# bGeigie3.net
KiCad netlist of a schematic drawn in EAGLE
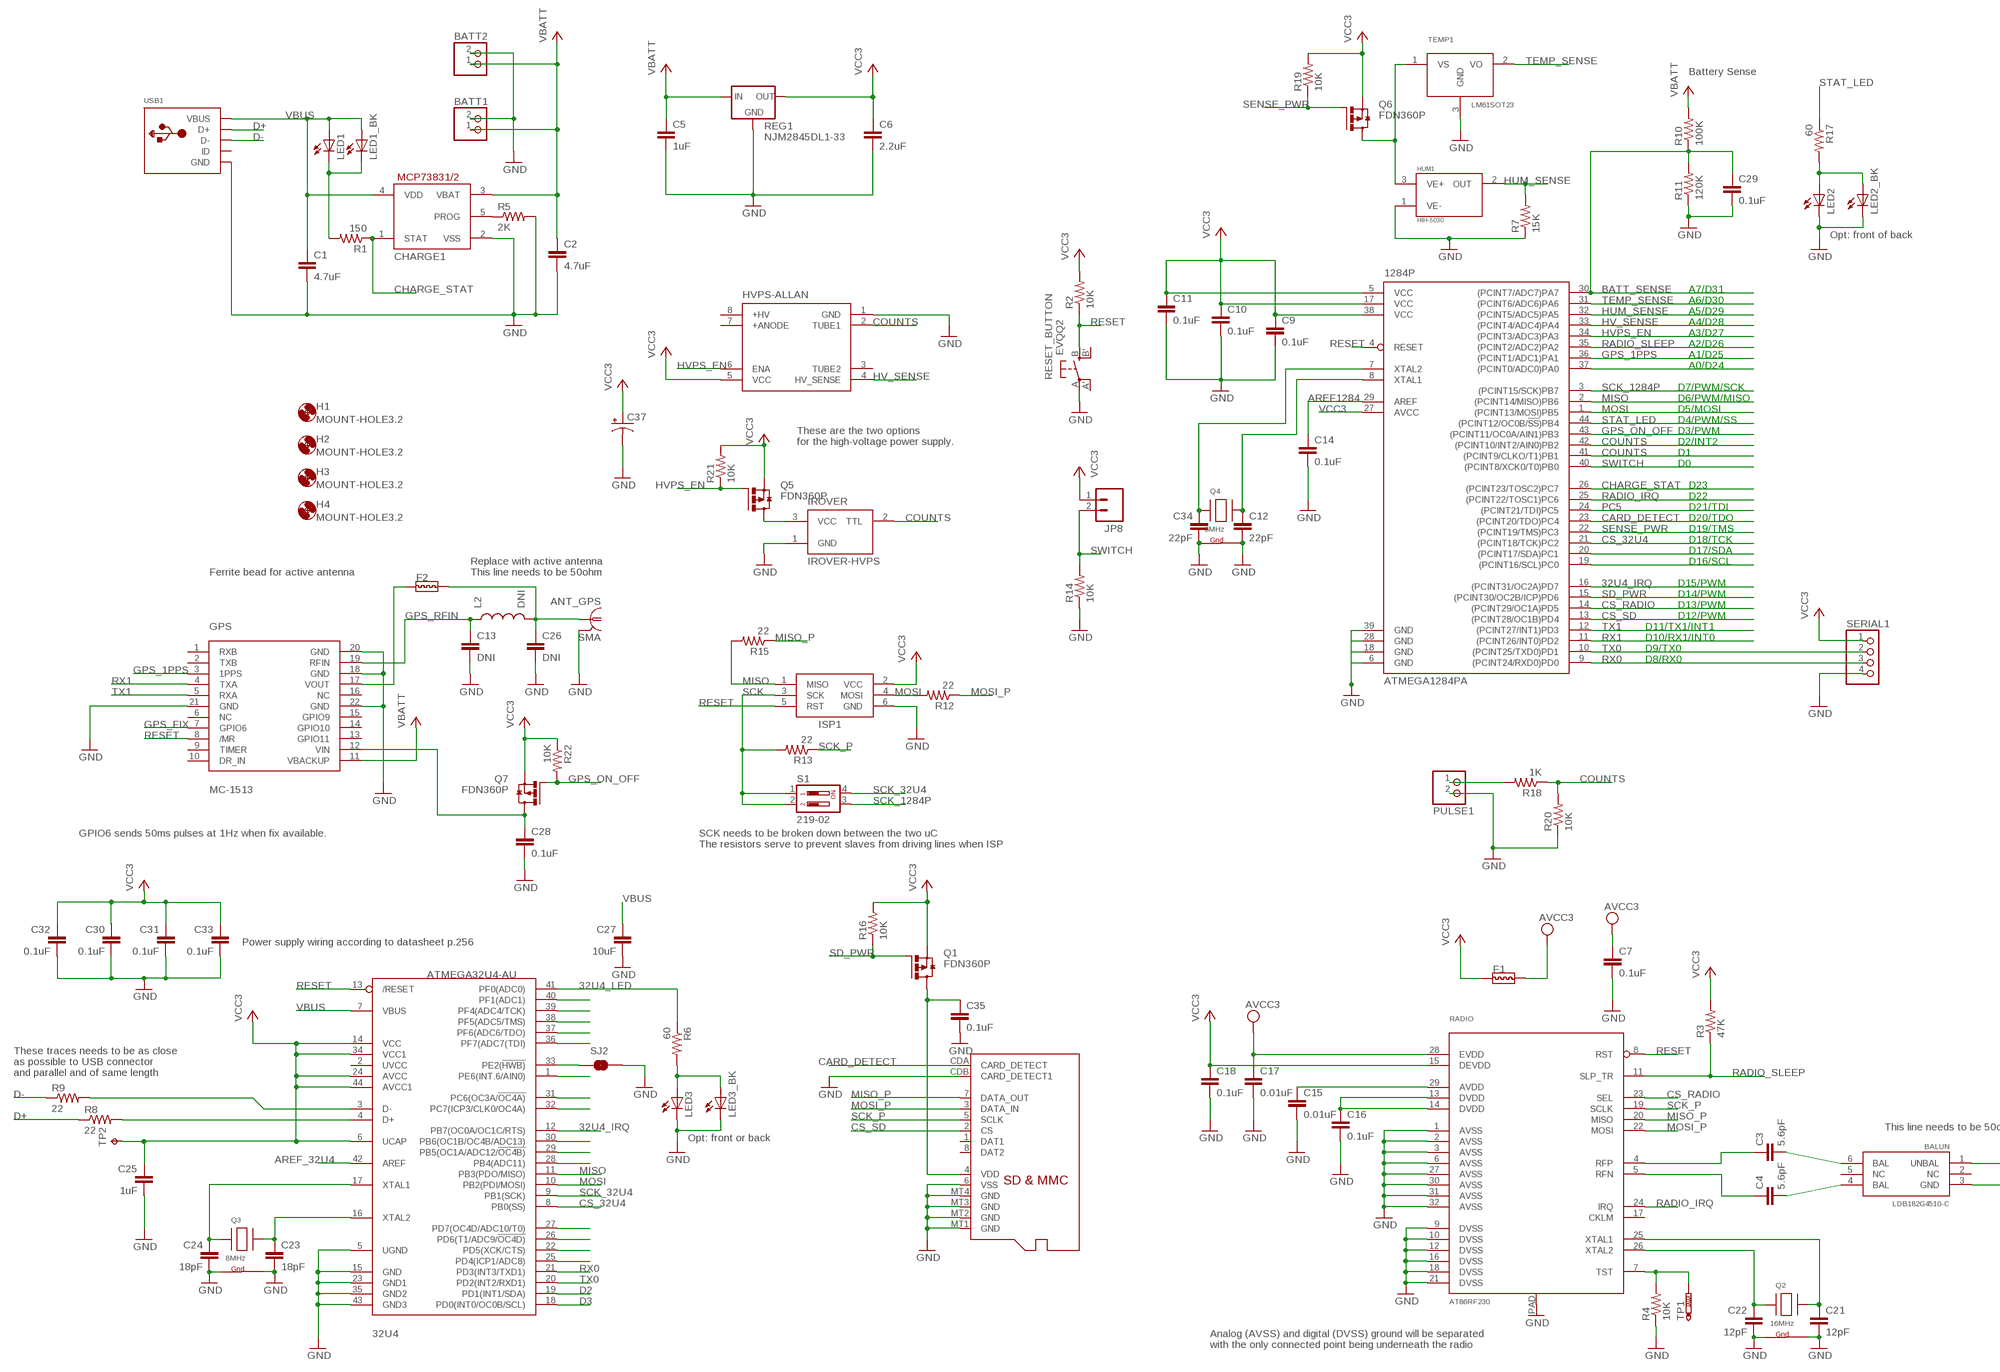
[diagram p0: schematic, sheet 1, part 1 of 2]
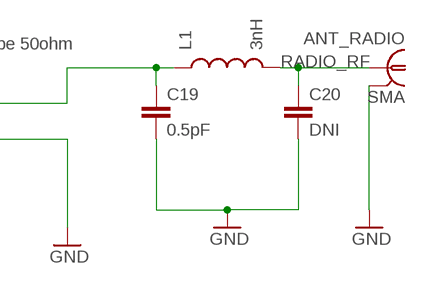
[diagram p1: schematic, sheet 1, part 2 of 2]

(export (version "E")
  (design (tool "Eeschema 10.0.6"))
  (components
    (comp (ref "32U4")
      (value "ATMEGA32U4-AU")
      (footprint "eagle-import:TQFP44")
      (libsource (lib "eagle-import") (part "ATMEGA32U4-AU"))
    )
    (comp (ref "1284P")
      (value "ATMEGA1284PA")
      (footprint "eagle-import:TQFP44")
      (fields (field (name "MPN") "ATMEGA644PV-10AU"))
      (libsource (lib "eagle-import") (part "ATMEGA1284PA"))
    )
    (comp (ref "ANT_GPS")
      (value "SMA")
      (footprint "eagle-import:LTI-SASF54GT")
      (libsource (lib "eagle-import") (part "LTI-SASF54GT"))
    )
    (comp (ref "ANT_RADIO")
      (value "SMA")
      (footprint "eagle-import:LTI-SASF54GT")
      (libsource (lib "eagle-import") (part "LTI-SASF54GT"))
    )
    (comp (ref "BALUN")
      (value "LDB182G4510-C")
      (footprint "eagle-import:LDB182G4510-C")
      (libsource (lib "eagle-import") (part "LDB182G4510-C"))
    )
    (comp (ref "BATT1")
      (value "JST_2PIN-THM")
      (footprint "eagle-import:JST-PH-2-THM")
      (libsource (lib "eagle-import") (part "JST_2PIN-THM"))
    )
    (comp (ref "BATT2")
      (value "JST_2PIN-THM")
      (footprint "eagle-import:JST-PH-2-THM")
      (libsource (lib "eagle-import") (part "JST_2PIN-THM"))
    )
    (comp (ref "C1")
      (value "4.7uF")
      (footprint "eagle-import:0805")
      (libsource (lib "eagle-import") (part "CAP0805"))
    )
    (comp (ref "C2")
      (value "4.7uF")
      (footprint "eagle-import:0805")
      (libsource (lib "eagle-import") (part "CAP0805"))
    )
    (comp (ref "C3")
      (value "5.6pF")
      (footprint "eagle-import:0402-CAP")
      (libsource (lib "eagle-import") (part "CAP0402-CAP"))
    )
    (comp (ref "C4")
      (value "5.6pF")
      (footprint "eagle-import:0402-CAP")
      (libsource (lib "eagle-import") (part "CAP0402-CAP"))
    )
    (comp (ref "C5")
      (value "1uF")
      (footprint "eagle-import:0805")
      (libsource (lib "eagle-import") (part "CAP0805"))
    )
    (comp (ref "C6")
      (value "2.2uF")
      (footprint "eagle-import:0805")
      (libsource (lib "eagle-import") (part "CAP0805"))
    )
    (comp (ref "C7")
      (value "0.1uF")
      (footprint "eagle-import:0603-CAP")
      (libsource (lib "eagle-import") (part "CAP0603-CAP"))
    )
    (comp (ref "C9")
      (value "0.1uF")
      (footprint "eagle-import:0603-CAP")
      (libsource (lib "eagle-import") (part "CAP0603-CAP"))
    )
    (comp (ref "C10")
      (value "0.1uF")
      (footprint "eagle-import:0603-CAP")
      (libsource (lib "eagle-import") (part "CAP0603-CAP"))
    )
    (comp (ref "C11")
      (value "0.1uF")
      (footprint "eagle-import:0603-CAP")
      (libsource (lib "eagle-import") (part "CAP0603-CAP"))
    )
    (comp (ref "C12")
      (value "22pF")
      (footprint "eagle-import:0603-CAP")
      (libsource (lib "eagle-import") (part "CAP0603-CAP"))
    )
    (comp (ref "C13")
      (value "DNI")
      (footprint "eagle-import:0402-CAP")
      (libsource (lib "eagle-import") (part "CAP0402-CAP"))
    )
    (comp (ref "C14")
      (value "0.1uF")
      (footprint "eagle-import:0603-CAP")
      (libsource (lib "eagle-import") (part "CAP0603-CAP"))
    )
    (comp (ref "C15")
      (value "0.01uF")
      (footprint "eagle-import:0603-CAP")
      (libsource (lib "eagle-import") (part "CAP0603-CAP"))
    )
    (comp (ref "C16")
      (value "0.1uF")
      (footprint "eagle-import:0603-CAP")
      (libsource (lib "eagle-import") (part "CAP0603-CAP"))
    )
    (comp (ref "C17")
      (value "0.01uF")
      (footprint "eagle-import:0603-CAP")
      (libsource (lib "eagle-import") (part "CAP0603-CAP"))
    )
    (comp (ref "C18")
      (value "0.1uF")
      (footprint "eagle-import:0603-CAP")
      (libsource (lib "eagle-import") (part "CAP0603-CAP"))
    )
    (comp (ref "C19")
      (value "0.5pF")
      (footprint "eagle-import:0402-CAP")
      (libsource (lib "eagle-import") (part "CAP0402-CAP"))
    )
    (comp (ref "C20")
      (value "DNI")
      (footprint "eagle-import:0402-CAP")
      (libsource (lib "eagle-import") (part "CAP0402-CAP"))
    )
    (comp (ref "C21")
      (value "12pF")
      (footprint "eagle-import:0603-CAP")
      (libsource (lib "eagle-import") (part "CAP0603-CAP"))
    )
    (comp (ref "C22")
      (value "12pF")
      (footprint "eagle-import:0603-CAP")
      (libsource (lib "eagle-import") (part "CAP0603-CAP"))
    )
    (comp (ref "C23")
      (value "18pF")
      (footprint "eagle-import:0603-CAP")
      (libsource (lib "eagle-import") (part "CAP0603-CAP"))
    )
    (comp (ref "C24")
      (value "18pF")
      (footprint "eagle-import:0603-CAP")
      (libsource (lib "eagle-import") (part "CAP0603-CAP"))
    )
    (comp (ref "C25")
      (value "1uF")
      (footprint "eagle-import:0603-CAP")
      (libsource (lib "eagle-import") (part "CAP0603-CAP"))
    )
    (comp (ref "C26")
      (value "DNI")
      (footprint "eagle-import:0402-CAP")
      (libsource (lib "eagle-import") (part "CAP0402-CAP"))
    )
    (comp (ref "C27")
      (value "10uF")
      (footprint "eagle-import:0805")
      (libsource (lib "eagle-import") (part "CAP0805"))
    )
    (comp (ref "C28")
      (value "0.1uF")
      (footprint "eagle-import:0603-CAP")
      (libsource (lib "eagle-import") (part "CAP0603-CAP"))
    )
    (comp (ref "C29")
      (value "0.1uF")
      (footprint "eagle-import:0603-CAP")
      (libsource (lib "eagle-import") (part "CAP0603-CAP"))
    )
    (comp (ref "C30")
      (value "0.1uF")
      (footprint "eagle-import:0603-CAP")
      (libsource (lib "eagle-import") (part "CAP0603-CAP"))
    )
    (comp (ref "C31")
      (value "0.1uF")
      (footprint "eagle-import:0603-CAP")
      (libsource (lib "eagle-import") (part "CAP0603-CAP"))
    )
    (comp (ref "C32")
      (value "0.1uF")
      (footprint "eagle-import:0603-CAP")
      (libsource (lib "eagle-import") (part "CAP0603-CAP"))
    )
    (comp (ref "C33")
      (value "0.1uF")
      (footprint "eagle-import:0603-CAP")
      (libsource (lib "eagle-import") (part "CAP0603-CAP"))
    )
    (comp (ref "C34")
      (value "22pF")
      (footprint "eagle-import:0603-CAP")
      (libsource (lib "eagle-import") (part "CAP0603-CAP"))
    )
    (comp (ref "C35")
      (value "0.1uF")
      (footprint "eagle-import:0603-CAP")
      (libsource (lib "eagle-import") (part "CAP0603-CAP"))
    )
    (comp (ref "C37")
      (value "CPOL-USD/7343-31W")
      (footprint "eagle-import:D_7343-31W")
      (libsource (lib "eagle-import") (part "CPOL-USD/7343-31W"))
    )
    (comp (ref "CHARGE1")
      (value "MCP73831/OT")
      (footprint "eagle-import:SOT23-5L")
      (libsource (lib "eagle-import") (part "MCP73831/OT"))
    )
    (comp (ref "F1")
      (value "L-FERRITE-BEAD-0805")
      (footprint "eagle-import:0805")
      (libsource (lib "eagle-import") (part "L-FERRITE-BEAD-0805"))
    )
    (comp (ref "F2")
      (value "L-FERRITE-BEAD-0805")
      (footprint "eagle-import:0805")
      (libsource (lib "eagle-import") (part "L-FERRITE-BEAD-0805"))
    )
    (comp (ref "GPS")
      (value "MC-1513")
      (footprint "eagle-import:S4-1513")
      (libsource (lib "eagle-import") (part "MC-1513"))
    )
    (comp (ref "H1")
      (value "MOUNT-HOLE3.2")
      (footprint "eagle-import:3,2")
      (libsource (lib "eagle-import") (part "MOUNT-HOLE3.2"))
    )
    (comp (ref "H2")
      (value "MOUNT-HOLE3.2")
      (footprint "eagle-import:3,2")
      (libsource (lib "eagle-import") (part "MOUNT-HOLE3.2"))
    )
    (comp (ref "H3")
      (value "MOUNT-HOLE3.2")
      (footprint "eagle-import:3,2")
      (libsource (lib "eagle-import") (part "MOUNT-HOLE3.2"))
    )
    (comp (ref "H4")
      (value "MOUNT-HOLE3.2")
      (footprint "eagle-import:3,2")
      (libsource (lib "eagle-import") (part "MOUNT-HOLE3.2"))
    )
    (comp (ref "HUM1")
      (value "HIH-5030")
      (footprint "eagle-import:HIH-5030")
      (libsource (lib "eagle-import") (part "HIH-5030"))
    )
    (comp (ref "HVPS-ALLAN")
      (value "HVPS-ALLANV2-REVERSE")
      (footprint "eagle-import:HVPS-ALLAN-V2-REVERSE")
      (libsource (lib "eagle-import") (part "HVPS-ALLANV2-REVERSE"))
    )
    (comp (ref "IROVER")
      (value "IROVER-HVPS")
      (footprint "eagle-import:IROVER")
      (libsource (lib "eagle-import") (part "IROVER-HVPS"))
    )
    (comp (ref "ISP1")
      (value "AVRISP-6")
      (footprint "eagle-import:AVRISP")
      (libsource (lib "eagle-import") (part "AVRISP-6"))
    )
    (comp (ref "JP8")
      (value "M023.5MM")
      (footprint "eagle-import:SCREWTERMINAL-3.5MM-2")
      (libsource (lib "eagle-import") (part "M023.5MM"))
    )
    (comp (ref "L1")
      (value "3nH")
      (footprint "eagle-import:C0402")
      (libsource (lib "eagle-import") (part "INDUCTOR0402"))
    )
    (comp (ref "L2")
      (value "DNI")
      (footprint "eagle-import:C0402")
      (libsource (lib "eagle-import") (part "INDUCTOR0402"))
    )
    (comp (ref "LED1")
      (value "LEDCHIPLED_0603")
      (footprint "eagle-import:CHIPLED_0603")
      (libsource (lib "eagle-import") (part "LEDCHIPLED_0603"))
    )
    (comp (ref "LED1_BK")
      (value "LEDCHIPLED_0603")
      (footprint "eagle-import:CHIPLED_0603")
      (libsource (lib "eagle-import") (part "LEDCHIPLED_0603"))
    )
    (comp (ref "LED2")
      (value "LEDCHIPLED_0603")
      (footprint "eagle-import:CHIPLED_0603")
      (libsource (lib "eagle-import") (part "LEDCHIPLED_0603"))
    )
    (comp (ref "LED2_BK")
      (value "LEDCHIPLED_0603")
      (footprint "eagle-import:CHIPLED_0603")
      (libsource (lib "eagle-import") (part "LEDCHIPLED_0603"))
    )
    (comp (ref "LED3")
      (value "LEDCHIPLED_0603")
      (footprint "eagle-import:CHIPLED_0603")
      (libsource (lib "eagle-import") (part "LEDCHIPLED_0603"))
    )
    (comp (ref "LED3_BK")
      (value "LEDCHIPLED_0603")
      (footprint "eagle-import:CHIPLED_0603")
      (libsource (lib "eagle-import") (part "LEDCHIPLED_0603"))
    )
    (comp (ref "PULSE1")
      (value "JST_2PIN-THM")
      (footprint "eagle-import:JST-PH-2-THM")
      (libsource (lib "eagle-import") (part "JST_2PIN-THM"))
    )
    (comp (ref "Q1")
      (value "FDN360P")
      (footprint "eagle-import:SUPER-SOT3")
      (libsource (lib "eagle-import") (part "FDN360P"))
    )
    (comp (ref "Q2")
      (value "16MHz")
      (footprint "eagle-import:NX3225")
      (libsource (lib "eagle-import") (part "XTAL-4-3225"))
    )
    (comp (ref "Q3")
      (value "8MHz")
      (footprint "eagle-import:CRYSTAL-5032")
      (libsource (lib "eagle-import") (part "XTAL-4"))
    )
    (comp (ref "Q4")
      (value "8MHz")
      (footprint "eagle-import:CRYSTAL-5032")
      (libsource (lib "eagle-import") (part "XTAL-4"))
    )
    (comp (ref "Q5")
      (value "FDN360P")
      (footprint "eagle-import:SUPER-SOT3")
      (libsource (lib "eagle-import") (part "FDN360P"))
    )
    (comp (ref "Q6")
      (value "FDN360P")
      (footprint "eagle-import:SUPER-SOT3")
      (libsource (lib "eagle-import") (part "FDN360P"))
    )
    (comp (ref "Q7")
      (value "FDN360P")
      (footprint "eagle-import:SUPER-SOT3")
      (libsource (lib "eagle-import") (part "FDN360P"))
    )
    (comp (ref "R1")
      (value "150")
      (footprint "eagle-import:R0805")
      (libsource (lib "eagle-import") (part "R-US_R0805"))
    )
    (comp (ref "R2")
      (value "10K")
      (footprint "eagle-import:R0603")
      (libsource (lib "eagle-import") (part "R-US_R0603"))
    )
    (comp (ref "R3")
      (value "47K")
      (footprint "eagle-import:R0603")
      (libsource (lib "eagle-import") (part "R-US_R0603"))
    )
    (comp (ref "R4")
      (value "10K")
      (footprint "eagle-import:R0603")
      (libsource (lib "eagle-import") (part "R-US_R0603"))
    )
    (comp (ref "R5")
      (value "2K")
      (footprint "eagle-import:R0603")
      (libsource (lib "eagle-import") (part "R-US_R0603"))
    )
    (comp (ref "R6")
      (value "60")
      (footprint "eagle-import:R0805")
      (libsource (lib "eagle-import") (part "R-US_R0805"))
    )
    (comp (ref "R7")
      (value "15K")
      (footprint "eagle-import:R0603")
      (libsource (lib "eagle-import") (part "R-US_R0603"))
    )
    (comp (ref "R8")
      (value "22")
      (footprint "eagle-import:R0603")
      (libsource (lib "eagle-import") (part "R-US_R0603"))
    )
    (comp (ref "R9")
      (value "22")
      (footprint "eagle-import:R0603")
      (libsource (lib "eagle-import") (part "R-US_R0603"))
    )
    (comp (ref "R10")
      (value "100K")
      (footprint "eagle-import:R0603")
      (libsource (lib "eagle-import") (part "R-US_R0603"))
    )
    (comp (ref "R11")
      (value "120K")
      (footprint "eagle-import:R0603")
      (libsource (lib "eagle-import") (part "R-US_R0603"))
    )
    (comp (ref "R12")
      (value "22")
      (footprint "eagle-import:R0603")
      (libsource (lib "eagle-import") (part "R-US_R0603"))
    )
    (comp (ref "R13")
      (value "22")
      (footprint "eagle-import:R0603")
      (libsource (lib "eagle-import") (part "R-US_R0603"))
    )
    (comp (ref "R14")
      (value "10K")
      (footprint "eagle-import:R0603")
      (libsource (lib "eagle-import") (part "R-US_R0603"))
    )
    (comp (ref "R15")
      (value "22")
      (footprint "eagle-import:R0603")
      (libsource (lib "eagle-import") (part "R-US_R0603"))
    )
    (comp (ref "R16")
      (value "10K")
      (footprint "eagle-import:R0603")
      (libsource (lib "eagle-import") (part "R-US_R0603"))
    )
    (comp (ref "R17")
      (value "60")
      (footprint "eagle-import:R0805")
      (libsource (lib "eagle-import") (part "R-US_R0805"))
    )
    (comp (ref "R18")
      (value "1K")
      (footprint "eagle-import:R0603")
      (libsource (lib "eagle-import") (part "R-US_R0603"))
    )
    (comp (ref "R19")
      (value "10K")
      (footprint "eagle-import:R0603")
      (libsource (lib "eagle-import") (part "R-US_R0603"))
    )
    (comp (ref "R20")
      (value "10K")
      (footprint "eagle-import:R0603")
      (libsource (lib "eagle-import") (part "R-US_R0603"))
    )
    (comp (ref "R21")
      (value "10K")
      (footprint "eagle-import:R0603")
      (libsource (lib "eagle-import") (part "R-US_R0603"))
    )
    (comp (ref "R22")
      (value "10K")
      (footprint "eagle-import:R0603")
      (libsource (lib "eagle-import") (part "R-US_R0603"))
    )
    (comp (ref "RADIO")
      (value "AT86RF230")
      (footprint "eagle-import:32QN1")
      (libsource (lib "eagle-import") (part "AT86RF230"))
    )
    (comp (ref "REG1")
      (value "NJM2845DL1-33")
      (footprint "eagle-import:DPACK")
      (libsource (lib "eagle-import") (part "LP2950?CDT-3.3"))
    )
    (comp (ref "RESET_BUTTON")
      (value "EVQQ2")
      (footprint "eagle-import:EVQ-Q2")
      (libsource (lib "eagle-import") (part "EVQQ2"))
    )
    (comp (ref "S1")
      (value "219-02")
      (footprint "eagle-import:CTS-219-02")
      (libsource (lib "eagle-import") (part "219-02"))
    )
    (comp (ref "SD")
      (value "MICROSD")
      (footprint "eagle-import:DM3AT-SF-PEJM5")
      (libsource (lib "eagle-import") (part "MICROSD"))
    )
    (comp (ref "SERIAL1")
      (value "PINHD-1X4")
      (footprint "eagle-import:1X04")
      (libsource (lib "eagle-import") (part "PINHD-1X4"))
    )
    (comp (ref "SJ2")
      (value "SOLDERJUMPERTRACE")
      (footprint "eagle-import:SJ_2S-TRACE")
      (libsource (lib "eagle-import") (part "SOLDERJUMPERTRACE"))
    )
    (comp (ref "TEMP1")
      (value "LM61SOT23")
      (footprint "eagle-import:SOT23")
      (libsource (lib "eagle-import") (part "LM61SOT23"))
    )
    (comp (ref "TP1")
      (value "PTR1B1,27")
      (footprint "eagle-import:B1,27")
      (libsource (lib "eagle-import") (part "PTR1B1,27"))
    )
    (comp (ref "TP2")
      (value "TPTP15SQ")
      (footprint "eagle-import:TP15SQ")
      (libsource (lib "eagle-import") (part "TPTP15SQ"))
    )
    (comp (ref "USB1")
      (value "USBMINIB")
      (footprint "eagle-import:USB-MINIB")
      (libsource (lib "eagle-import") (part "USBMINIB"))
    )
  )
  (nets
    (net (code "1") (name "/32U4_IRQ") (class "Default")
      (node (ref "1284P") (pin "16") (pinfunction "(PCINT31/OC2A)PD7_16") (pintype "bidirectional"))
      (node (ref "32U4") (pin "12") (pinfunction "PB7(OC0A/OC1C/RTS)_12") (pintype "bidirectional"))
    )
    (net (code "2") (name "/32U4_LED") (class "Default")
      (node (ref "32U4") (pin "41") (pinfunction "PF0(ADC0)_41") (pintype "bidirectional"))
      (node (ref "R6") (pin "1") (pinfunction "1_1") (pintype "passive"))
    )
    (net (code "3") (name "/AREF1284") (class "Default")
      (node (ref "1284P") (pin "29") (pinfunction "AREF_29") (pintype "passive"))
      (node (ref "C14") (pin "1") (pinfunction "1_1") (pintype "passive"))
    )
    (net (code "4") (name "/AREF_32U4") (class "Default")
      (node (ref "32U4") (pin "42") (pinfunction "AREF_42") (pintype "bidirectional"))
    )
    (net (code "5") (name "/BATT_SENSE") (class "Default")
      (node (ref "1284P") (pin "30") (pinfunction "(PCINT7/ADC7)PA7_30") (pintype "bidirectional"))
      (node (ref "C29") (pin "1") (pinfunction "1_1") (pintype "passive"))
      (node (ref "R10") (pin "1") (pinfunction "1_1") (pintype "passive"))
      (node (ref "R11") (pin "2") (pinfunction "2_2") (pintype "passive"))
    )
    (net (code "6") (name "/CARD_DETECT") (class "Default")
      (node (ref "1284P") (pin "23") (pinfunction "(PCINT20/TDO)PC4_23") (pintype "output"))
      (node (ref "SD") (pin "CDA") (pinfunction "CARD_DETECT_CDA") (pintype "passive"))
    )
    (net (code "7") (name "/CHARGE_STAT") (class "Default")
      (node (ref "1284P") (pin "26") (pinfunction "(PCINT23/TOSC2)PC7_26") (pintype "output"))
      (node (ref "CHARGE1") (pin "1") (pinfunction "STAT_1") (pintype "output"))
      (node (ref "R1") (pin "1") (pinfunction "1_1") (pintype "passive"))
    )
    (net (code "8") (name "/COUNTS") (class "Default")
      (node (ref "1284P") (pin "41") (pinfunction "(PCINT9/CLKO/T1)PB1_41") (pintype "bidirectional"))
      (node (ref "1284P") (pin "42") (pinfunction "(PCINT10/INT2/AIN0)PB2_42") (pintype "bidirectional"))
      (node (ref "HVPS-ALLAN") (pin "2") (pinfunction "TUBE1_2") (pintype "bidirectional"))
      (node (ref "IROVER") (pin "2") (pinfunction "TTL_2") (pintype "bidirectional"))
      (node (ref "R18") (pin "1") (pinfunction "1_1") (pintype "passive"))
      (node (ref "R20") (pin "2") (pinfunction "2_2") (pintype "passive"))
    )
    (net (code "9") (name "/CS_32U4") (class "Default")
      (node (ref "1284P") (pin "21") (pinfunction "(PCINT18/TCK)PC2_21") (pintype "output"))
      (node (ref "32U4") (pin "8") (pinfunction "PB0(SS)_8") (pintype "bidirectional"))
    )
    (net (code "10") (name "/CS_RADIO") (class "Default")
      (node (ref "1284P") (pin "14") (pinfunction "(PCINT29/OC1A)PD5_14") (pintype "bidirectional"))
      (node (ref "RADIO") (pin "23") (pinfunction "SEL_23") (pintype "bidirectional"))
    )
    (net (code "11") (name "/CS_SD") (class "Default")
      (node (ref "1284P") (pin "13") (pinfunction "(PCINT28/OC1B)PD4_13") (pintype "bidirectional"))
      (node (ref "SD") (pin "2") (pinfunction "CS_2") (pintype "input"))
    )
    (net (code "12") (name "/D+") (class "Default")
      (node (ref "R8") (pin "1") (pinfunction "1_1") (pintype "passive"))
      (node (ref "USB1") (pin "D+") (pinfunction "D+_D+") (pintype "bidirectional"))
    )
    (net (code "13") (name "/D-") (class "Default")
      (node (ref "R9") (pin "1") (pinfunction "1_1") (pintype "passive"))
      (node (ref "USB1") (pin "D-") (pinfunction "D-_D-") (pintype "bidirectional"))
    )
    (net (code "14") (name "/D2") (class "Default")
      (node (ref "32U4") (pin "19") (pinfunction "PD1(INT1/SDA)_19") (pintype "bidirectional"))
    )
    (net (code "15") (name "/D3") (class "Default")
      (node (ref "32U4") (pin "18") (pinfunction "PD0(INT0/OC0B/SCL)_18") (pintype "bidirectional"))
    )
    (net (code "16") (name "/GPS_1PPS") (class "Default")
      (node (ref "1284P") (pin "36") (pinfunction "(PCINT1/ADC1)PA1_36") (pintype "bidirectional"))
      (node (ref "GPS") (pin "3") (pinfunction "1PPS_3") (pintype "bidirectional"))
    )
    (net (code "17") (name "/GPS_FIX") (class "Default")
      (node (ref "GPS") (pin "7") (pinfunction "GPIO6_7") (pintype "bidirectional"))
    )
    (net (code "18") (name "/GPS_ON_OFF") (class "Default")
      (node (ref "1284P") (pin "43") (pinfunction "(PCINT11/OC0A/AIN1)PB3_43") (pintype "bidirectional"))
      (node (ref "Q7") (pin "1") (pinfunction "G_1") (pintype "passive"))
      (node (ref "R22") (pin "2") (pinfunction "2_2") (pintype "passive"))
    )
    (net (code "19") (name "/GPS_RFIN") (class "Default")
      (node (ref "C13") (pin "1") (pinfunction "1_1") (pintype "passive"))
      (node (ref "GPS") (pin "19") (pinfunction "RFIN_19") (pintype "bidirectional"))
      (node (ref "L2") (pin "1") (pinfunction "1_1") (pintype "passive"))
    )
    (net (code "20") (name "/HUM_SENSE") (class "Default")
      (node (ref "1284P") (pin "32") (pinfunction "(PCINT5/ADC5)PA5_32") (pintype "bidirectional"))
      (node (ref "HUM1") (pin "2") (pinfunction "OUT_2") (pintype "bidirectional"))
      (node (ref "R7") (pin "2") (pinfunction "2_2") (pintype "passive"))
    )
    (net (code "21") (name "/HVPS_EN") (class "Default")
      (node (ref "1284P") (pin "34") (pinfunction "(PCINT3/ADC3)PA3_34") (pintype "bidirectional"))
      (node (ref "HVPS-ALLAN") (pin "6") (pinfunction "ENA_6") (pintype "bidirectional"))
      (node (ref "Q5") (pin "1") (pinfunction "G_1") (pintype "passive"))
      (node (ref "R21") (pin "1") (pinfunction "1_1") (pintype "passive"))
    )
    (net (code "22") (name "/HV_SENSE") (class "Default")
      (node (ref "1284P") (pin "33") (pinfunction "(PCINT4/ADC4)PA4_33") (pintype "bidirectional"))
      (node (ref "HVPS-ALLAN") (pin "4") (pinfunction "HV_SENSE_4") (pintype "bidirectional"))
    )
    (net (code "23") (name "/MISO") (class "Default")
      (node (ref "1284P") (pin "2") (pinfunction "(PCINT14/MISO)PB6_2") (pintype "bidirectional"))
      (node (ref "32U4") (pin "11") (pinfunction "PB3(PDO/MISO)_11") (pintype "bidirectional"))
      (node (ref "ISP1") (pin "1") (pinfunction "MISO_1") (pintype "input"))
      (node (ref "R15") (pin "2") (pinfunction "2_2") (pintype "passive"))
    )
    (net (code "24") (name "/MISO_P") (class "Default")
      (node (ref "R15") (pin "1") (pinfunction "1_1") (pintype "passive"))
      (node (ref "RADIO") (pin "20") (pinfunction "MISO_20") (pintype "bidirectional"))
      (node (ref "SD") (pin "7") (pinfunction "DATA_OUT_7") (pintype "output"))
    )
    (net (code "25") (name "/MOSI") (class "Default")
      (node (ref "1284P") (pin "1") (pinfunction "(PCINT13/MOSI)PB5_1") (pintype "bidirectional"))
      (node (ref "32U4") (pin "10") (pinfunction "PB2(PDI/MOSI)_10") (pintype "bidirectional"))
      (node (ref "ISP1") (pin "4") (pinfunction "MOSI_4") (pintype "output"))
      (node (ref "R12") (pin "2") (pinfunction "2_2") (pintype "passive"))
    )
    (net (code "26") (name "/MOSI_P") (class "Default")
      (node (ref "R12") (pin "1") (pinfunction "1_1") (pintype "passive"))
      (node (ref "RADIO") (pin "22") (pinfunction "MOSI_22") (pintype "bidirectional"))
      (node (ref "SD") (pin "3") (pinfunction "DATA_IN_3") (pintype "input"))
    )
    (net (code "27") (name "/PC5") (class "Default")
      (node (ref "1284P") (pin "24") (pinfunction "(PCINT21/TDI)PC5_24") (pintype "output"))
    )
    (net (code "28") (name "/RADIO_IRQ") (class "Default")
      (node (ref "1284P") (pin "25") (pinfunction "(PCINT22/TOSC1)PC6_25") (pintype "output"))
      (node (ref "RADIO") (pin "24") (pinfunction "IRQ_24") (pintype "bidirectional"))
    )
    (net (code "29") (name "/RADIO_RF") (class "Default")
      (node (ref "ANT_RADIO") (pin "1") (pinfunction "1_1") (pintype "passive"))
      (node (ref "C20") (pin "1") (pinfunction "1_1") (pintype "passive"))
      (node (ref "L1") (pin "2") (pinfunction "2_2") (pintype "passive"))
    )
    (net (code "30") (name "/RADIO_SLEEP") (class "Default")
      (node (ref "1284P") (pin "35") (pinfunction "(PCINT2/ADC2)PA2_35") (pintype "bidirectional"))
      (node (ref "R3") (pin "1") (pinfunction "1_1") (pintype "passive"))
      (node (ref "RADIO") (pin "11") (pinfunction "SLP_TR_11") (pintype "bidirectional"))
    )
    (net (code "31") (name "/RESET") (class "Default")
      (node (ref "1284P") (pin "4") (pinfunction "RESET_4") (pintype "input"))
      (node (ref "32U4") (pin "13") (pinfunction "/RESET_13") (pintype "bidirectional"))
      (node (ref "GPS") (pin "8") (pinfunction "/MR_8") (pintype "bidirectional"))
      (node (ref "ISP1") (pin "5") (pinfunction "RST_5") (pintype "output"))
      (node (ref "R2") (pin "1") (pinfunction "1_1") (pintype "passive"))
      (node (ref "RADIO") (pin "8") (pinfunction "RST_8") (pintype "input"))
      (node (ref "RESET_BUTTON") (pin "B") (pinfunction "S_B") (pintype "passive"))
    )
    (net (code "32") (name "/RX0") (class "Default")
      (node (ref "1284P") (pin "9") (pinfunction "(PCINT24/RXD0)PD0_9") (pintype "bidirectional"))
      (node (ref "32U4") (pin "21") (pinfunction "PD3(INT3/TXD1)_21") (pintype "bidirectional"))
      (node (ref "SERIAL1") (pin "3") (pinfunction "3_3") (pintype "passive"))
    )
    (net (code "33") (name "/RX1") (class "Default")
      (node (ref "1284P") (pin "11") (pinfunction "(PCINT26/INT0)PD2_11") (pintype "bidirectional"))
      (node (ref "GPS") (pin "4") (pinfunction "TXA_4") (pintype "bidirectional"))
    )
    (net (code "34") (name "/SCK") (class "Default")
      (node (ref "ISP1") (pin "3") (pinfunction "SCK_3") (pintype "output"))
      (node (ref "R13") (pin "2") (pinfunction "2_2") (pintype "passive"))
      (node (ref "S1") (pin "1") (pinfunction "1_1") (pintype "passive"))
      (node (ref "S1") (pin "2") (pinfunction "2_2") (pintype "passive"))
    )
    (net (code "35") (name "/SCK_32U4") (class "Default")
      (node (ref "32U4") (pin "9") (pinfunction "PB1(SCK)_9") (pintype "bidirectional"))
      (node (ref "S1") (pin "4") (pinfunction "4_4") (pintype "passive"))
    )
    (net (code "36") (name "/SCK_1284P") (class "Default")
      (node (ref "1284P") (pin "3") (pinfunction "(PCINT15/SCK)PB7_3") (pintype "bidirectional"))
      (node (ref "S1") (pin "3") (pinfunction "3_3") (pintype "passive"))
    )
    (net (code "37") (name "/SCK_P") (class "Default")
      (node (ref "R13") (pin "1") (pinfunction "1_1") (pintype "passive"))
      (node (ref "RADIO") (pin "19") (pinfunction "SCLK_19") (pintype "bidirectional"))
      (node (ref "SD") (pin "5") (pinfunction "SCLK_5") (pintype "input"))
    )
    (net (code "38") (name "/SD_PWR") (class "Default")
      (node (ref "1284P") (pin "15") (pinfunction "(PCINT30/OC2B/ICP)PD6_15") (pintype "bidirectional"))
      (node (ref "Q1") (pin "1") (pinfunction "G_1") (pintype "passive"))
      (node (ref "R16") (pin "1") (pinfunction "1_1") (pintype "passive"))
    )
    (net (code "39") (name "/SENSE_PWR") (class "Default")
      (node (ref "1284P") (pin "22") (pinfunction "(PCINT19/TMS)PC3_22") (pintype "output"))
      (node (ref "Q6") (pin "1") (pinfunction "G_1") (pintype "passive"))
      (node (ref "R19") (pin "1") (pinfunction "1_1") (pintype "passive"))
    )
    (net (code "40") (name "/STAT_LED") (class "Default")
      (node (ref "1284P") (pin "44") (pinfunction "(PCINT12/OC0B/~{SS})PB4_44") (pintype "bidirectional"))
      (node (ref "R17") (pin "1") (pinfunction "1_1") (pintype "passive"))
    )
    (net (code "41") (name "/SWITCH") (class "Default")
      (node (ref "1284P") (pin "40") (pinfunction "(PCINT8/XCK0/T0)PB0_40") (pintype "bidirectional"))
      (node (ref "JP8") (pin "2") (pinfunction "2_2") (pintype "passive"))
      (node (ref "R14") (pin "2") (pinfunction "2_2") (pintype "passive"))
    )
    (net (code "42") (name "/TEMP_SENSE") (class "Default")
      (node (ref "1284P") (pin "31") (pinfunction "(PCINT6/ADC6)PA6_31") (pintype "bidirectional"))
      (node (ref "TEMP1") (pin "2") (pinfunction "VO_2") (pintype "bidirectional"))
    )
    (net (code "43") (name "/TX0") (class "Default")
      (node (ref "1284P") (pin "10") (pinfunction "(PCINT25/TXD0)PD1_10") (pintype "bidirectional"))
      (node (ref "32U4") (pin "20") (pinfunction "PD2(INT2/RXD1)_20") (pintype "bidirectional"))
      (node (ref "SERIAL1") (pin "2") (pinfunction "2_2") (pintype "passive"))
    )
    (net (code "44") (name "/TX1") (class "Default")
      (node (ref "1284P") (pin "12") (pinfunction "(PCINT27/INT1)PD3_12") (pintype "bidirectional"))
      (node (ref "GPS") (pin "5") (pinfunction "RXA_5") (pintype "bidirectional"))
    )
    (net (code "45") (name "/VBUS") (class "Default")
      (node (ref "32U4") (pin "7") (pinfunction "VBUS_7") (pintype "bidirectional"))
      (node (ref "C1") (pin "1") (pinfunction "1_1") (pintype "passive"))
      (node (ref "C27") (pin "1") (pinfunction "1_1") (pintype "passive"))
      (node (ref "CHARGE1") (pin "4") (pinfunction "VDD_4") (pintype "power_in"))
      (node (ref "LED1") (pin "A") (pinfunction "A_A") (pintype "passive"))
      (node (ref "LED1_BK") (pin "A") (pinfunction "A_A") (pintype "passive"))
      (node (ref "USB1") (pin "VBUS") (pinfunction "VBUS_VBUS") (pintype "power_in"))
    )
    (net (code "46") (name "AVCC3") (class "Default")
      (node (ref "C17") (pin "1") (pinfunction "1_1") (pintype "passive"))
      (node (ref "C7") (pin "1") (pinfunction "1_1") (pintype "passive"))
      (node (ref "F1") (pin "2") (pinfunction "2_2") (pintype "bidirectional"))
      (node (ref "RADIO") (pin "28") (pinfunction "EVDD_28") (pintype "bidirectional"))
    )
    (net (code "47") (name "GND") (class "Default")
      (node (ref "1284P") (pin "18") (pinfunction "GND_18") (pintype "power_in"))
      (node (ref "1284P") (pin "28") (pinfunction "GND_28") (pintype "power_in"))
      (node (ref "1284P") (pin "39") (pinfunction "GND_39") (pintype "power_in"))
      (node (ref "1284P") (pin "6") (pinfunction "GND_6") (pintype "power_in"))
      (node (ref "32U4") (pin "15") (pinfunction "GND_15") (pintype "bidirectional"))
      (node (ref "32U4") (pin "23") (pinfunction "GND1_23") (pintype "bidirectional"))
      (node (ref "32U4") (pin "35") (pinfunction "GND2_35") (pintype "bidirectional"))
      (node (ref "32U4") (pin "43") (pinfunction "GND3_43") (pintype "bidirectional"))
      (node (ref "32U4") (pin "5") (pinfunction "UGND_5") (pintype "bidirectional"))
      (node (ref "ANT_GPS") (pin "2") (pinfunction "GND_2") (pintype "power_in"))
      (node (ref "ANT_RADIO") (pin "2") (pinfunction "GND_2") (pintype "power_in"))
      (node (ref "BALUN") (pin "3") (pinfunction "GND_3") (pintype "bidirectional"))
      (node (ref "BATT1") (pin "2") (pinfunction "1_2") (pintype "passive"))
      (node (ref "BATT2") (pin "2") (pinfunction "1_2") (pintype "passive"))
      (node (ref "C1") (pin "2") (pinfunction "2_2") (pintype "passive"))
      (node (ref "C10") (pin "2") (pinfunction "2_2") (pintype "passive"))
      (node (ref "C11") (pin "2") (pinfunction "2_2") (pintype "passive"))
      (node (ref "C12") (pin "2") (pinfunction "2_2") (pintype "passive"))
      (node (ref "C13") (pin "2") (pinfunction "2_2") (pintype "passive"))
      (node (ref "C14") (pin "2") (pinfunction "2_2") (pintype "passive"))
      (node (ref "C15") (pin "2") (pinfunction "2_2") (pintype "passive"))
      (node (ref "C16") (pin "2") (pinfunction "2_2") (pintype "passive"))
      (node (ref "C17") (pin "2") (pinfunction "2_2") (pintype "passive"))
      (node (ref "C18") (pin "2") (pinfunction "2_2") (pintype "passive"))
      (node (ref "C19") (pin "2") (pinfunction "2_2") (pintype "passive"))
      (node (ref "C2") (pin "2") (pinfunction "2_2") (pintype "passive"))
      (node (ref "C20") (pin "2") (pinfunction "2_2") (pintype "passive"))
      (node (ref "C21") (pin "2") (pinfunction "2_2") (pintype "passive"))
      (node (ref "C22") (pin "2") (pinfunction "2_2") (pintype "passive"))
      (node (ref "C23") (pin "2") (pinfunction "2_2") (pintype "passive"))
      (node (ref "C24") (pin "2") (pinfunction "2_2") (pintype "passive"))
      (node (ref "C25") (pin "2") (pinfunction "2_2") (pintype "passive"))
      (node (ref "C26") (pin "2") (pinfunction "2_2") (pintype "passive"))
      (node (ref "C27") (pin "2") (pinfunction "2_2") (pintype "passive"))
      (node (ref "C28") (pin "2") (pinfunction "2_2") (pintype "passive"))
      (node (ref "C29") (pin "2") (pinfunction "2_2") (pintype "passive"))
      (node (ref "C30") (pin "2") (pinfunction "2_2") (pintype "passive"))
      (node (ref "C31") (pin "2") (pinfunction "2_2") (pintype "passive"))
      (node (ref "C32") (pin "2") (pinfunction "2_2") (pintype "passive"))
      (node (ref "C33") (pin "2") (pinfunction "2_2") (pintype "passive"))
      (node (ref "C34") (pin "2") (pinfunction "2_2") (pintype "passive"))
      (node (ref "C35") (pin "2") (pinfunction "2_2") (pintype "passive"))
      (node (ref "C37") (pin "-") (pinfunction "-_-") (pintype "passive"))
      (node (ref "C5") (pin "2") (pinfunction "2_2") (pintype "passive"))
      (node (ref "C6") (pin "2") (pinfunction "2_2") (pintype "passive"))
      (node (ref "C7") (pin "2") (pinfunction "2_2") (pintype "passive"))
      (node (ref "C9") (pin "2") (pinfunction "2_2") (pintype "passive"))
      (node (ref "CHARGE1") (pin "2") (pinfunction "VSS_2") (pintype "power_in"))
      (node (ref "GPS") (pin "18") (pinfunction "GND_18") (pintype "bidirectional"))
      (node (ref "GPS") (pin "20") (pinfunction "GND_20") (pintype "bidirectional"))
      (node (ref "GPS") (pin "21") (pinfunction "GND_21") (pintype "bidirectional"))
      (node (ref "GPS") (pin "22") (pinfunction "GND_22") (pintype "bidirectional"))
      (node (ref "HUM1") (pin "1") (pinfunction "VE-_1") (pintype "bidirectional"))
      (node (ref "HVPS-ALLAN") (pin "1") (pinfunction "GND_1") (pintype "bidirectional"))
      (node (ref "IROVER") (pin "1") (pinfunction "GND_1") (pintype "power_in"))
      (node (ref "ISP1") (pin "6") (pinfunction "GND_6") (pintype "power_in"))
      (node (ref "LED2") (pin "C") (pinfunction "C_C") (pintype "passive"))
      (node (ref "LED2_BK") (pin "C") (pinfunction "C_C") (pintype "passive"))
      (node (ref "LED3") (pin "C") (pinfunction "C_C") (pintype "passive"))
      (node (ref "LED3_BK") (pin "C") (pinfunction "C_C") (pintype "passive"))
      (node (ref "PULSE1") (pin "2") (pinfunction "1_2") (pintype "passive"))
      (node (ref "Q2") (pin "2") (pinfunction "G2_2") (pintype "power_in"))
      (node (ref "Q2") (pin "4") (pinfunction "G1_4") (pintype "power_in"))
      (node (ref "Q3") (pin "2") (pinfunction "G1_2") (pintype "power_in"))
      (node (ref "Q3") (pin "4") (pinfunction "G2_4") (pintype "power_in"))
      (node (ref "Q4") (pin "2") (pinfunction "G1_2") (pintype "power_in"))
      (node (ref "Q4") (pin "4") (pinfunction "G2_4") (pintype "power_in"))
      (node (ref "R11") (pin "1") (pinfunction "1_1") (pintype "passive"))
      (node (ref "R14") (pin "1") (pinfunction "1_1") (pintype "passive"))
      (node (ref "R20") (pin "1") (pinfunction "1_1") (pintype "passive"))
      (node (ref "R4") (pin "1") (pinfunction "1_1") (pintype "passive"))
      (node (ref "R5") (pin "2") (pinfunction "2_2") (pintype "passive"))
      (node (ref "R7") (pin "1") (pinfunction "1_1") (pintype "passive"))
      (node (ref "RADIO") (pin "1") (pinfunction "AVSS_1") (pintype "bidirectional"))
      (node (ref "RADIO") (pin "10") (pinfunction "DVSS_10") (pintype "bidirectional"))
      (node (ref "RADIO") (pin "12") (pinfunction "DVSS_12") (pintype "bidirectional"))
      (node (ref "RADIO") (pin "16") (pinfunction "DVSS_16") (pintype "bidirectional"))
      (node (ref "RADIO") (pin "18") (pinfunction "DVSS_18") (pintype "bidirectional"))
      (node (ref "RADIO") (pin "2") (pinfunction "AVSS_2") (pintype "bidirectional"))
      (node (ref "RADIO") (pin "21") (pinfunction "DVSS_21") (pintype "bidirectional"))
      (node (ref "RADIO") (pin "27") (pinfunction "AVSS_27") (pintype "bidirectional"))
      (node (ref "RADIO") (pin "3") (pinfunction "AVSS_3") (pintype "bidirectional"))
      (node (ref "RADIO") (pin "30") (pinfunction "AVSS_30") (pintype "bidirectional"))
      (node (ref "RADIO") (pin "31") (pinfunction "AVSS_31") (pintype "bidirectional"))
      (node (ref "RADIO") (pin "32") (pinfunction "AVSS_32") (pintype "bidirectional"))
      (node (ref "RADIO") (pin "6") (pinfunction "AVSS_6") (pintype "bidirectional"))
      (node (ref "RADIO") (pin "9") (pinfunction "DVSS_9") (pintype "bidirectional"))
      (node (ref "RADIO") (pin "PAD") (pinfunction "PAD_PAD") (pintype "power_in"))
      (node (ref "REG1") (pin "4") (pinfunction "GND_4") (pintype "input"))
      (node (ref "RESET_BUTTON") (pin "A") (pinfunction "P_A") (pintype "passive"))
      (node (ref "SD") (pin "6") (pinfunction "VSS_6") (pintype "power_in"))
      (node (ref "SD") (pin "CDB") (pinfunction "CARD_DETECT1_CDB") (pintype "passive"))
      (node (ref "SD") (pin "MT1") (pinfunction "GND_MT1") (pintype "power_in"))
      (node (ref "SD") (pin "MT2") (pinfunction "GND_MT2") (pintype "power_in"))
      (node (ref "SD") (pin "MT3") (pinfunction "GND_MT3") (pintype "power_in"))
      (node (ref "SD") (pin "MT4") (pinfunction "GND_MT4") (pintype "power_in"))
      (node (ref "SERIAL1") (pin "4") (pinfunction "4_4") (pintype "passive"))
      (node (ref "SJ2") (pin "2") (pinfunction "2_2") (pintype "passive"))
      (node (ref "TEMP1") (pin "3") (pinfunction "GND_3") (pintype "bidirectional"))
      (node (ref "USB1") (pin "GND") (pinfunction "GND_GND") (pintype "power_in"))
    )
    (net (code "48") (name "Net-(32U4-D+)") (class "Default")
      (node (ref "32U4") (pin "4") (pinfunction "D+_4") (pintype "bidirectional"))
      (node (ref "R8") (pin "2") (pinfunction "2_2") (pintype "passive"))
    )
    (net (code "49") (name "Net-(32U4-D-)") (class "Default")
      (node (ref "32U4") (pin "3") (pinfunction "D-_3") (pintype "bidirectional"))
      (node (ref "R9") (pin "2") (pinfunction "2_2") (pintype "passive"))
    )
    (net (code "50") (name "Net-(32U4-PE2(~{HWB}))") (class "Default")
      (node (ref "32U4") (pin "33") (pinfunction "PE2(~{HWB})_33") (pintype "bidirectional"))
      (node (ref "SJ2") (pin "1") (pinfunction "1_1") (pintype "passive"))
    )
    (net (code "51") (name "Net-(32U4-XTAL1)") (class "Default")
      (node (ref "32U4") (pin "17") (pinfunction "XTAL1_17") (pintype "bidirectional"))
      (node (ref "C24") (pin "1") (pinfunction "1_1") (pintype "passive"))
      (node (ref "Q3") (pin "1") (pinfunction "X1_1") (pintype "bidirectional"))
    )
    (net (code "52") (name "Net-(32U4-XTAL2)") (class "Default")
      (node (ref "32U4") (pin "16") (pinfunction "XTAL2_16") (pintype "bidirectional"))
      (node (ref "C23") (pin "1") (pinfunction "1_1") (pintype "passive"))
      (node (ref "Q3") (pin "3") (pinfunction "X2_3") (pintype "bidirectional"))
    )
    (net (code "53") (name "Net-(1284P-XTAL1)") (class "Default")
      (node (ref "1284P") (pin "8") (pinfunction "XTAL1_8") (pintype "bidirectional"))
      (node (ref "C12") (pin "1") (pinfunction "1_1") (pintype "passive"))
      (node (ref "Q4") (pin "3") (pinfunction "X2_3") (pintype "bidirectional"))
    )
    (net (code "54") (name "Net-(1284P-XTAL2)") (class "Default")
      (node (ref "1284P") (pin "7") (pinfunction "XTAL2_7") (pintype "bidirectional"))
      (node (ref "C34") (pin "1") (pinfunction "1_1") (pintype "passive"))
      (node (ref "Q4") (pin "1") (pinfunction "X1_1") (pintype "bidirectional"))
    )
    (net (code "55") (name "Net-(ANT_GPS-Pad1)") (class "Default")
      (node (ref "ANT_GPS") (pin "1") (pinfunction "1_1") (pintype "passive"))
      (node (ref "C26") (pin "1") (pinfunction "1_1") (pintype "passive"))
      (node (ref "F2") (pin "2") (pinfunction "2_2") (pintype "bidirectional"))
      (node (ref "L2") (pin "2") (pinfunction "2_2") (pintype "passive"))
    )
    (net (code "56") (name "Net-(BALUN-BAL-Pad4)") (class "Default")
      (node (ref "BALUN") (pin "4") (pinfunction "BAL_4") (pintype "bidirectional"))
      (node (ref "C4") (pin "2") (pinfunction "2_2") (pintype "passive"))
    )
    (net (code "57") (name "Net-(BALUN-BAL-Pad6)") (class "Default")
      (node (ref "BALUN") (pin "6") (pinfunction "BAL_6") (pintype "bidirectional"))
      (node (ref "C3") (pin "2") (pinfunction "2_2") (pintype "passive"))
    )
    (net (code "58") (name "Net-(BALUN-UNBAL)") (class "Default")
      (node (ref "BALUN") (pin "1") (pinfunction "UNBAL_1") (pintype "bidirectional"))
      (node (ref "C19") (pin "1") (pinfunction "1_1") (pintype "passive"))
      (node (ref "L1") (pin "1") (pinfunction "1_1") (pintype "passive"))
    )
    (net (code "59") (name "Net-(C16-Pad1)") (class "Default")
      (node (ref "C16") (pin "1") (pinfunction "1_1") (pintype "passive"))
      (node (ref "RADIO") (pin "13") (pinfunction "DVDD_13") (pintype "bidirectional"))
      (node (ref "RADIO") (pin "14") (pinfunction "DVDD_14") (pintype "bidirectional"))
    )
    (net (code "60") (name "Net-(CHARGE1-PROG)") (class "Default")
      (node (ref "CHARGE1") (pin "5") (pinfunction "PROG_5") (pintype "input"))
      (node (ref "R5") (pin "1") (pinfunction "1_1") (pintype "passive"))
    )
    (net (code "61") (name "Net-(GPS-VIN)") (class "Default")
      (node (ref "C28") (pin "1") (pinfunction "1_1") (pintype "passive"))
      (node (ref "GPS") (pin "12") (pinfunction "VIN_12") (pintype "bidirectional"))
      (node (ref "Q7") (pin "3") (pinfunction "D_3") (pintype "passive"))
    )
    (net (code "62") (name "Net-(GPS-VOUT)") (class "Default")
      (node (ref "F2") (pin "1") (pinfunction "1_1") (pintype "bidirectional"))
      (node (ref "GPS") (pin "17") (pinfunction "VOUT_17") (pintype "bidirectional"))
    )
    (net (code "63") (name "Net-(HUM1-VE+)") (class "Default")
      (node (ref "HUM1") (pin "3") (pinfunction "VE+_3") (pintype "bidirectional"))
      (node (ref "Q6") (pin "3") (pinfunction "D_3") (pintype "passive"))
      (node (ref "TEMP1") (pin "1") (pinfunction "VS_1") (pintype "bidirectional"))
    )
    (net (code "64") (name "Net-(IROVER-VCC)") (class "Default")
      (node (ref "IROVER") (pin "3") (pinfunction "VCC_3") (pintype "power_in"))
      (node (ref "Q5") (pin "3") (pinfunction "D_3") (pintype "passive"))
    )
    (net (code "65") (name "Net-(LED1-PadC)") (class "Default")
      (node (ref "LED1") (pin "C") (pinfunction "C_C") (pintype "passive"))
      (node (ref "LED1_BK") (pin "C") (pinfunction "C_C") (pintype "passive"))
      (node (ref "R1") (pin "2") (pinfunction "2_2") (pintype "passive"))
    )
    (net (code "66") (name "Net-(LED2-PadA)") (class "Default")
      (node (ref "LED2") (pin "A") (pinfunction "A_A") (pintype "passive"))
      (node (ref "LED2_BK") (pin "A") (pinfunction "A_A") (pintype "passive"))
      (node (ref "R17") (pin "2") (pinfunction "2_2") (pintype "passive"))
    )
    (net (code "67") (name "Net-(LED3-PadA)") (class "Default")
      (node (ref "LED3") (pin "A") (pinfunction "A_A") (pintype "passive"))
      (node (ref "LED3_BK") (pin "A") (pinfunction "A_A") (pintype "passive"))
      (node (ref "R6") (pin "2") (pinfunction "2_2") (pintype "passive"))
    )
    (net (code "68") (name "Net-(PULSE1-2)") (class "Default")
      (node (ref "PULSE1") (pin "1") (pinfunction "2_1") (pintype "passive"))
      (node (ref "R18") (pin "2") (pinfunction "2_2") (pintype "passive"))
    )
    (net (code "69") (name "Net-(Q1-D)") (class "Default")
      (node (ref "C35") (pin "1") (pinfunction "1_1") (pintype "passive"))
      (node (ref "Q1") (pin "3") (pinfunction "D_3") (pintype "passive"))
      (node (ref "SD") (pin "4") (pinfunction "VDD_4") (pintype "power_in"))
    )
    (net (code "70") (name "Net-(Q2-X1)") (class "Default")
      (node (ref "C22") (pin "1") (pinfunction "1_1") (pintype "passive"))
      (node (ref "Q2") (pin "1") (pinfunction "X1_1") (pintype "bidirectional"))
      (node (ref "RADIO") (pin "26") (pinfunction "XTAL2_26") (pintype "bidirectional"))
    )
    (net (code "71") (name "Net-(Q2-X2)") (class "Default")
      (node (ref "C21") (pin "1") (pinfunction "1_1") (pintype "passive"))
      (node (ref "Q2") (pin "3") (pinfunction "X2_3") (pintype "bidirectional"))
      (node (ref "RADIO") (pin "25") (pinfunction "XTAL1_25") (pintype "bidirectional"))
    )
    (net (code "72") (name "Net-(RADIO-AVDD)") (class "Default")
      (node (ref "C15") (pin "1") (pinfunction "1_1") (pintype "passive"))
      (node (ref "RADIO") (pin "29") (pinfunction "AVDD_29") (pintype "bidirectional"))
    )
    (net (code "73") (name "Net-(RADIO-RFN)") (class "Default")
      (node (ref "C4") (pin "1") (pinfunction "1_1") (pintype "passive"))
      (node (ref "RADIO") (pin "5") (pinfunction "RFN_5") (pintype "bidirectional"))
    )
    (net (code "74") (name "Net-(RADIO-RFP)") (class "Default")
      (node (ref "C3") (pin "1") (pinfunction "1_1") (pintype "passive"))
      (node (ref "RADIO") (pin "4") (pinfunction "RFP_4") (pintype "bidirectional"))
    )
    (net (code "75") (name "Net-(RADIO-TST)") (class "Default")
      (node (ref "R4") (pin "2") (pinfunction "2_2") (pintype "passive"))
      (node (ref "RADIO") (pin "7") (pinfunction "TST_7") (pintype "bidirectional"))
      (node (ref "TP1") (pin "TP") (pinfunction "TP_TP") (pintype "input"))
    )
    (net (code "76") (name "VBATT") (class "Default")
      (node (ref "BATT1") (pin "1") (pinfunction "2_1") (pintype "passive"))
      (node (ref "BATT2") (pin "1") (pinfunction "2_1") (pintype "passive"))
      (node (ref "C2") (pin "1") (pinfunction "1_1") (pintype "passive"))
      (node (ref "C5") (pin "1") (pinfunction "1_1") (pintype "passive"))
      (node (ref "CHARGE1") (pin "3") (pinfunction "VBAT_3") (pintype "bidirectional"))
      (node (ref "GPS") (pin "11") (pinfunction "VBACKUP_11") (pintype "bidirectional"))
      (node (ref "R10") (pin "2") (pinfunction "2_2") (pintype "passive"))
      (node (ref "REG1") (pin "1") (pinfunction "IN_1") (pintype "input"))
    )
    (net (code "77") (name "VCC3") (class "Default")
      (node (ref "1284P") (pin "17") (pinfunction "VCC_17") (pintype "power_in"))
      (node (ref "1284P") (pin "27") (pinfunction "AVCC_27") (pintype "power_in"))
      (node (ref "1284P") (pin "38") (pinfunction "VCC_38") (pintype "power_in"))
      (node (ref "1284P") (pin "5") (pinfunction "VCC_5") (pintype "power_in"))
      (node (ref "32U4") (pin "14") (pinfunction "VCC_14") (pintype "bidirectional"))
      (node (ref "32U4") (pin "24") (pinfunction "AVCC_24") (pintype "bidirectional"))
      (node (ref "32U4") (pin "34") (pinfunction "VCC1_34") (pintype "bidirectional"))
      (node (ref "32U4") (pin "44") (pinfunction "AVCC1_44") (pintype "bidirectional"))
      (node (ref "32U4") (pin "6") (pinfunction "UCAP_6") (pintype "bidirectional"))
      (node (ref "C10") (pin "1") (pinfunction "1_1") (pintype "passive"))
      (node (ref "C11") (pin "1") (pinfunction "1_1") (pintype "passive"))
      (node (ref "C18") (pin "1") (pinfunction "1_1") (pintype "passive"))
      (node (ref "C25") (pin "1") (pinfunction "1_1") (pintype "passive"))
      (node (ref "C30") (pin "1") (pinfunction "1_1") (pintype "passive"))
      (node (ref "C31") (pin "1") (pinfunction "1_1") (pintype "passive"))
      (node (ref "C32") (pin "1") (pinfunction "1_1") (pintype "passive"))
      (node (ref "C33") (pin "1") (pinfunction "1_1") (pintype "passive"))
      (node (ref "C37") (pin "+") (pinfunction "+_+") (pintype "passive"))
      (node (ref "C6") (pin "1") (pinfunction "1_1") (pintype "passive"))
      (node (ref "C9") (pin "1") (pinfunction "1_1") (pintype "passive"))
      (node (ref "F1") (pin "1") (pinfunction "1_1") (pintype "bidirectional"))
      (node (ref "HVPS-ALLAN") (pin "5") (pinfunction "VCC_5") (pintype "bidirectional"))
      (node (ref "ISP1") (pin "2") (pinfunction "VCC_2") (pintype "power_in"))
      (node (ref "JP8") (pin "1") (pinfunction "1_1") (pintype "passive"))
      (node (ref "Q1") (pin "2") (pinfunction "S_2") (pintype "passive"))
      (node (ref "Q5") (pin "2") (pinfunction "S_2") (pintype "passive"))
      (node (ref "Q6") (pin "2") (pinfunction "S_2") (pintype "passive"))
      (node (ref "Q7") (pin "2") (pinfunction "S_2") (pintype "passive"))
      (node (ref "R16") (pin "2") (pinfunction "2_2") (pintype "passive"))
      (node (ref "R19") (pin "2") (pinfunction "2_2") (pintype "passive"))
      (node (ref "R2") (pin "2") (pinfunction "2_2") (pintype "passive"))
      (node (ref "R21") (pin "2") (pinfunction "2_2") (pintype "passive"))
      (node (ref "R22") (pin "1") (pinfunction "1_1") (pintype "passive"))
      (node (ref "R3") (pin "2") (pinfunction "2_2") (pintype "passive"))
      (node (ref "RADIO") (pin "15") (pinfunction "DEVDD_15") (pintype "bidirectional"))
      (node (ref "REG1") (pin "3") (pinfunction "OUT_3") (pintype "passive"))
      (node (ref "SERIAL1") (pin "1") (pinfunction "1_1") (pintype "passive"))
      (node (ref "TP2") (pin "TP") (pinfunction "TP_TP") (pintype "input"))
    )
    (net (code "78") (name "unconnected-(32U4-PB4(ADC11)-Pad28)") (class "Default")
      (node (ref "32U4") (pin "28") (pinfunction "PB4(ADC11)_28") (pintype "bidirectional"))
    )
    (net (code "79") (name "unconnected-(32U4-PB5(OC1A{slash}ADC12{slash}~{OC4B})-Pad29)") (class "Default")
      (node (ref "32U4") (pin "29") (pinfunction "PB5(OC1A/ADC12/~{OC4B})_29") (pintype "bidirectional"))
    )
    (net (code "80") (name "unconnected-(32U4-PB6(OC1B{slash}OC4B{slash}ADC13)-Pad30)") (class "Default")
      (node (ref "32U4") (pin "30") (pinfunction "PB6(OC1B/OC4B/ADC13)_30") (pintype "bidirectional"))
    )
    (net (code "81") (name "unconnected-(32U4-PC6(OC3A{slash}~{OC4A})-Pad31)") (class "Default")
      (node (ref "32U4") (pin "31") (pinfunction "PC6(OC3A/~{OC4A})_31") (pintype "bidirectional"))
    )
    (net (code "82") (name "unconnected-(32U4-PC7(ICP3{slash}CLK0{slash}OC4A)-Pad32)") (class "Default")
      (node (ref "32U4") (pin "32") (pinfunction "PC7(ICP3/CLK0/OC4A)_32") (pintype "bidirectional"))
    )
    (net (code "83") (name "unconnected-(32U4-PD4(ICP1{slash}ADC8)-Pad25)") (class "Default")
      (node (ref "32U4") (pin "25") (pinfunction "PD4(ICP1/ADC8)_25") (pintype "bidirectional"))
    )
    (net (code "84") (name "unconnected-(32U4-PD5(XCK{slash}CTS)-Pad22)") (class "Default")
      (node (ref "32U4") (pin "22") (pinfunction "PD5(XCK/CTS)_22") (pintype "bidirectional"))
    )
    (net (code "85") (name "unconnected-(32U4-PD6(T1{slash}ADC9{slash}~{OC4D})-Pad26)") (class "Default")
      (node (ref "32U4") (pin "26") (pinfunction "PD6(T1/ADC9/~{OC4D})_26") (pintype "bidirectional"))
    )
    (net (code "86") (name "unconnected-(32U4-PD7(OC4D{slash}ADC10{slash}T0)-Pad27)") (class "Default")
      (node (ref "32U4") (pin "27") (pinfunction "PD7(OC4D/ADC10/T0)_27") (pintype "bidirectional"))
    )
    (net (code "87") (name "unconnected-(32U4-PE6(INT.6{slash}AIN0)-Pad1)") (class "Default")
      (node (ref "32U4") (pin "1") (pinfunction "PE6(INT.6/AIN0)_1") (pintype "bidirectional"))
    )
    (net (code "88") (name "unconnected-(32U4-PF1(ADC1)-Pad40)") (class "Default")
      (node (ref "32U4") (pin "40") (pinfunction "PF1(ADC1)_40") (pintype "bidirectional"))
    )
    (net (code "89") (name "unconnected-(32U4-PF4(ADC4{slash}TCK)-Pad39)") (class "Default")
      (node (ref "32U4") (pin "39") (pinfunction "PF4(ADC4/TCK)_39") (pintype "bidirectional"))
    )
    (net (code "90") (name "unconnected-(32U4-PF5(ADC5{slash}TMS)-Pad38)") (class "Default")
      (node (ref "32U4") (pin "38") (pinfunction "PF5(ADC5/TMS)_38") (pintype "bidirectional"))
    )
    (net (code "91") (name "unconnected-(32U4-PF6(ADC6{slash}TDO)-Pad37)") (class "Default")
      (node (ref "32U4") (pin "37") (pinfunction "PF6(ADC6/TDO)_37") (pintype "bidirectional"))
    )
    (net (code "92") (name "unconnected-(32U4-PF7(ADC7(TDI)-Pad36)") (class "Default")
      (node (ref "32U4") (pin "36") (pinfunction "PF7(ADC7(TDI)_36") (pintype "bidirectional"))
    )
    (net (code "93") (name "unconnected-(32U4-UVCC-Pad2)") (class "Default")
      (node (ref "32U4") (pin "2") (pinfunction "UVCC_2") (pintype "bidirectional"))
    )
    (net (code "94") (name "unconnected-(1284P-(PCINT0{slash}ADC0)PA0-Pad37)") (class "Default")
      (node (ref "1284P") (pin "37") (pinfunction "(PCINT0/ADC0)PA0_37") (pintype "bidirectional"))
    )
    (net (code "95") (name "unconnected-(1284P-(PCINT16{slash}SCL)PC0-Pad19)") (class "Default")
      (node (ref "1284P") (pin "19") (pinfunction "(PCINT16/SCL)PC0_19") (pintype "output"))
    )
    (net (code "96") (name "unconnected-(1284P-(PCINT17{slash}SDA)PC1-Pad20)") (class "Default")
      (node (ref "1284P") (pin "20") (pinfunction "(PCINT17/SDA)PC1_20") (pintype "output"))
    )
    (net (code "97") (name "unconnected-(BALUN-NC-Pad2)") (class "Default")
      (node (ref "BALUN") (pin "2") (pinfunction "NC_2") (pintype "bidirectional"))
    )
    (net (code "98") (name "unconnected-(BALUN-NC-Pad5)") (class "Default")
      (node (ref "BALUN") (pin "5") (pinfunction "NC_5") (pintype "bidirectional"))
    )
    (net (code "99") (name "unconnected-(GPS-DR_IN-Pad10)") (class "Default")
      (node (ref "GPS") (pin "10") (pinfunction "DR_IN_10") (pintype "bidirectional"))
    )
    (net (code "100") (name "unconnected-(GPS-GPIO9-Pad15)") (class "Default")
      (node (ref "GPS") (pin "15") (pinfunction "GPIO9_15") (pintype "bidirectional"))
    )
    (net (code "101") (name "unconnected-(GPS-GPIO10-Pad14)") (class "Default")
      (node (ref "GPS") (pin "14") (pinfunction "GPIO10_14") (pintype "bidirectional"))
    )
    (net (code "102") (name "unconnected-(GPS-GPIO11-Pad13)") (class "Default")
      (node (ref "GPS") (pin "13") (pinfunction "GPIO11_13") (pintype "bidirectional"))
    )
    (net (code "103") (name "unconnected-(GPS-NC-Pad6)") (class "Default")
      (node (ref "GPS") (pin "6") (pinfunction "NC_6") (pintype "bidirectional"))
    )
    (net (code "104") (name "unconnected-(GPS-NC-Pad16)") (class "Default")
      (node (ref "GPS") (pin "16") (pinfunction "NC_16") (pintype "bidirectional"))
    )
    (net (code "105") (name "unconnected-(GPS-RXB-Pad1)") (class "Default")
      (node (ref "GPS") (pin "1") (pinfunction "RXB_1") (pintype "bidirectional"))
    )
    (net (code "106") (name "unconnected-(GPS-TIMER-Pad9)") (class "Default")
      (node (ref "GPS") (pin "9") (pinfunction "TIMER_9") (pintype "bidirectional"))
    )
    (net (code "107") (name "unconnected-(GPS-TXB-Pad2)") (class "Default")
      (node (ref "GPS") (pin "2") (pinfunction "TXB_2") (pintype "bidirectional"))
    )
    (net (code "108") (name "unconnected-(HVPS-ALLAN-+ANODE-Pad7)") (class "Default")
      (node (ref "HVPS-ALLAN") (pin "7") (pinfunction "+ANODE_7") (pintype "bidirectional"))
    )
    (net (code "109") (name "unconnected-(HVPS-ALLAN-+HV-Pad8)") (class "Default")
      (node (ref "HVPS-ALLAN") (pin "8") (pinfunction "+HV_8") (pintype "bidirectional"))
    )
    (net (code "110") (name "unconnected-(HVPS-ALLAN-TUBE2-Pad3)") (class "Default")
      (node (ref "HVPS-ALLAN") (pin "3") (pinfunction "TUBE2_3") (pintype "bidirectional"))
    )
    (net (code "111") (name "unconnected-(RADIO-CKLM-Pad17)") (class "Default")
      (node (ref "RADIO") (pin "17") (pinfunction "CKLM_17") (pintype "bidirectional"))
    )
    (net (code "112") (name "unconnected-(RESET_BUTTON-P1-PadA')") (class "Default")
      (node (ref "RESET_BUTTON") (pin "A'") (pinfunction "P1_A'") (pintype "passive"))
    )
    (net (code "113") (name "unconnected-(RESET_BUTTON-S1-PadB')") (class "Default")
      (node (ref "RESET_BUTTON") (pin "B'") (pinfunction "S1_B'") (pintype "passive"))
    )
    (net (code "114") (name "unconnected-(SD-DAT1-Pad1)") (class "Default")
      (node (ref "SD") (pin "1") (pinfunction "DAT1_1") (pintype "bidirectional"))
    )
    (net (code "115") (name "unconnected-(SD-DAT2-Pad8)") (class "Default")
      (node (ref "SD") (pin "8") (pinfunction "DAT2_8") (pintype "bidirectional"))
    )
    (net (code "116") (name "unconnected-(USB1-PadID)") (class "Default")
      (node (ref "USB1") (pin "ID") (pinfunction "ID_ID") (pintype "bidirectional"))
    )
  )
)
